# asserv-pami.net
KiCad netlist of a schematic drawn in EAGLE
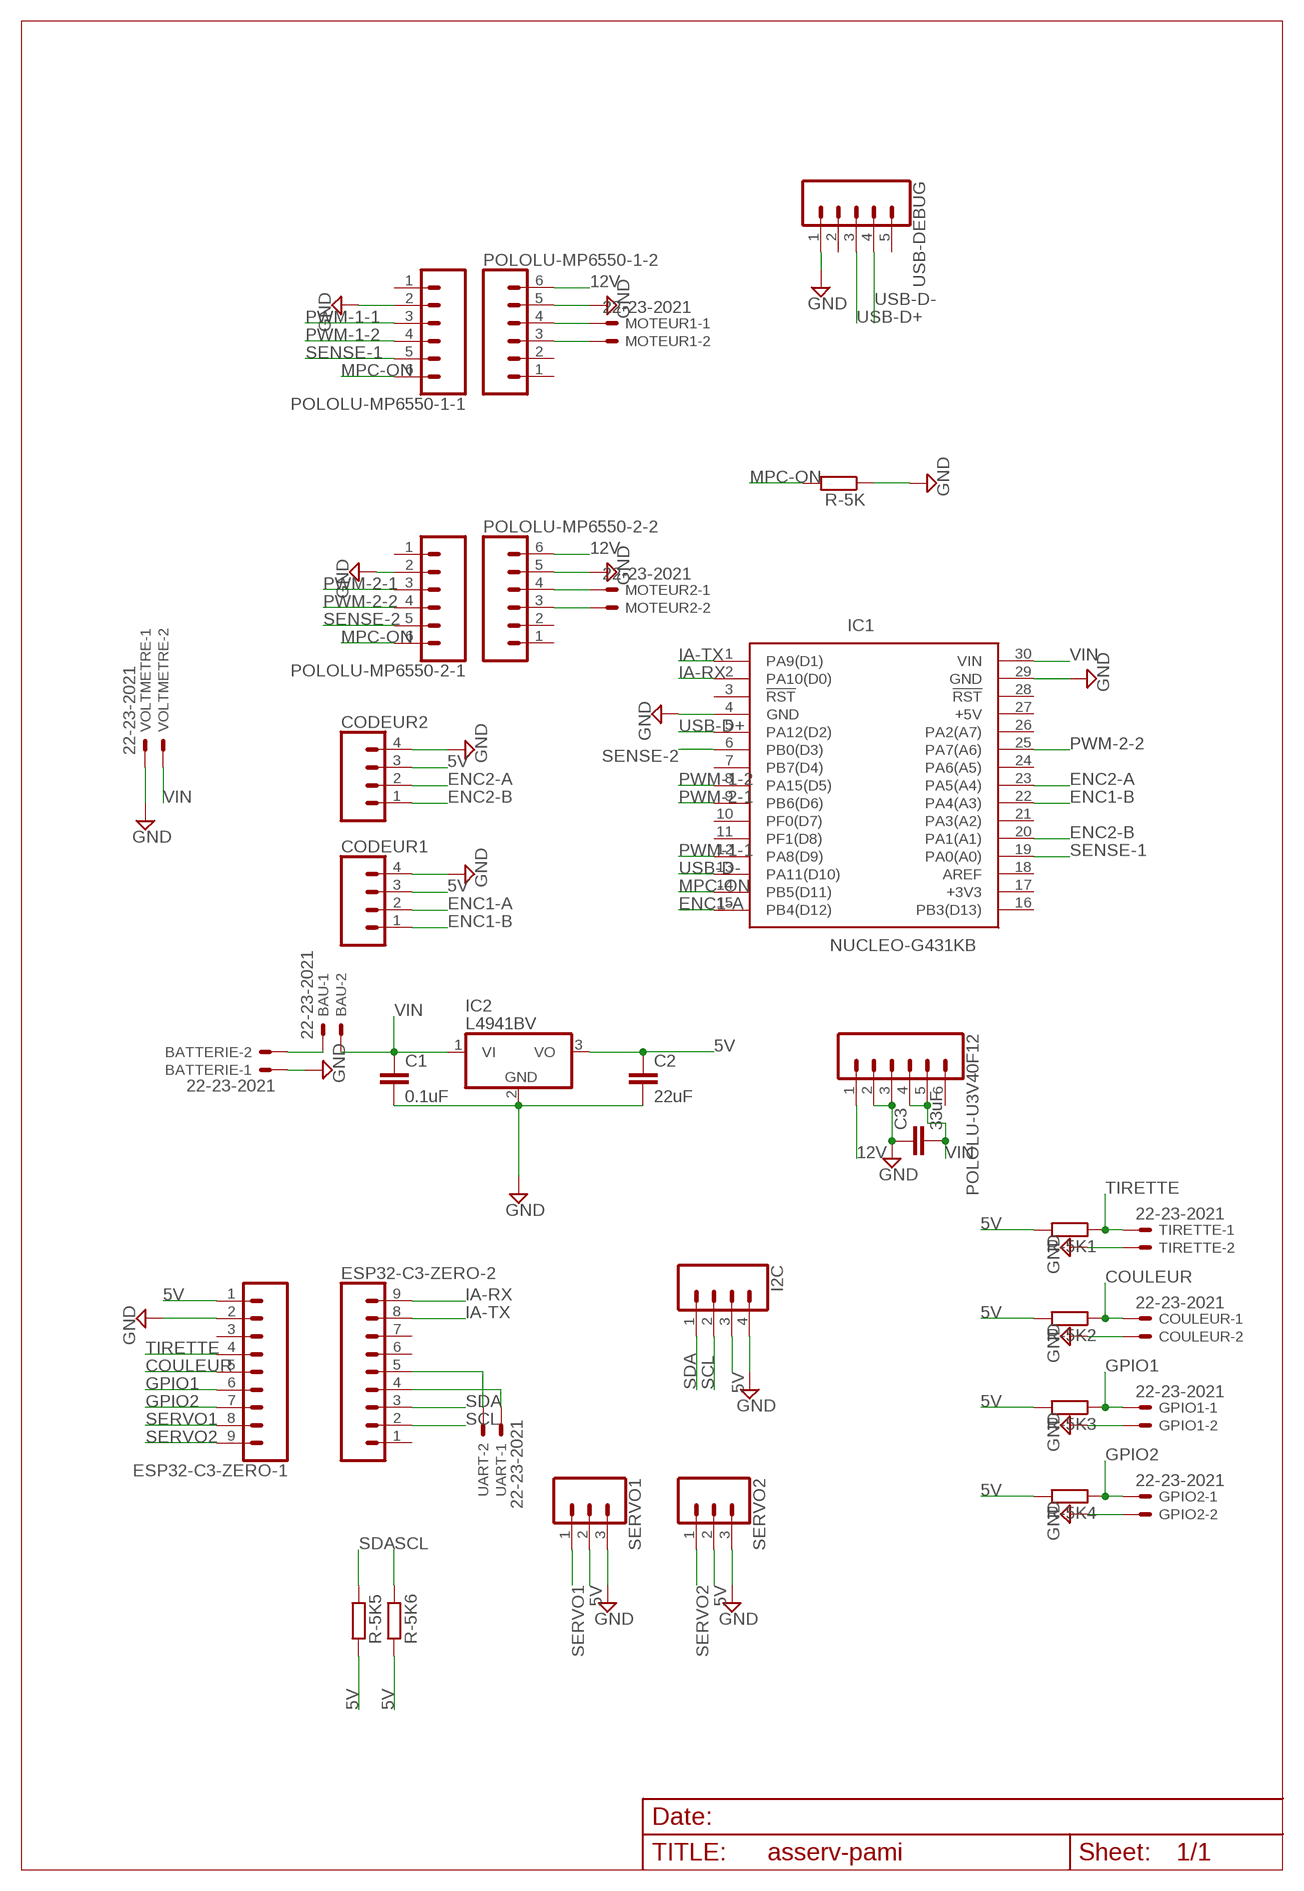
[diagram p0: schematic, sheet 1]

(export (version "E")
  (design (tool "Eeschema 10.0.6"))
  (components
    (comp (ref "BATTERIE")
      (value "22-23-2021")
      (footprint "eagle-import:22-23-2021")
      (fields (field (name "MF") "MOLEX"))
      (libsource (lib "eagle-import") (part "22-23-2021"))
    )
    (comp (ref "BAU")
      (value "22-23-2021")
      (footprint "eagle-import:22-23-2021")
      (fields (field (name "MF") "MOLEX"))
      (libsource (lib "eagle-import") (part "22-23-2021"))
    )
    (comp (ref "C1")
      (value "0.1uF")
      (footprint "eagle-import:C5B2.5")
      (libsource (lib "eagle-import") (part "C5/2.5"))
    )
    (comp (ref "C2")
      (value "22uF")
      (footprint "eagle-import:C5B2.5")
      (libsource (lib "eagle-import") (part "C5/2.5"))
    )
    (comp (ref "C3")
      (value "33uF")
      (footprint "eagle-import:C5B2.5")
      (libsource (lib "eagle-import") (part "C5/2.5"))
    )
    (comp (ref "CODEUR1")
      (value "CONN_04PTH")
      (footprint "eagle-import:1X04")
      (libsource (lib "eagle-import") (part "CONN_04PTH"))
    )
    (comp (ref "CODEUR2")
      (value "CONN_04PTH")
      (footprint "eagle-import:1X04")
      (libsource (lib "eagle-import") (part "CONN_04PTH"))
    )
    (comp (ref "COULEUR")
      (value "22-23-2021")
      (footprint "eagle-import:22-23-2021")
      (fields (field (name "MF") "MOLEX"))
      (libsource (lib "eagle-import") (part "22-23-2021"))
    )
    (comp (ref "ESP32-C3-ZERO-1")
      (value "CONN_09LONGPADS")
      (footprint "eagle-import:1X09_LONGPADS")
      (libsource (lib "eagle-import") (part "CONN_09LONGPADS"))
    )
    (comp (ref "ESP32-C3-ZERO-2")
      (value "CONN_09LONGPADS")
      (footprint "eagle-import:1X09_LONGPADS")
      (libsource (lib "eagle-import") (part "CONN_09LONGPADS"))
    )
    (comp (ref "GPIO1")
      (value "22-23-2021")
      (footprint "eagle-import:22-23-2021")
      (fields (field (name "MF") "MOLEX"))
      (libsource (lib "eagle-import") (part "22-23-2021"))
    )
    (comp (ref "GPIO2")
      (value "22-23-2021")
      (footprint "eagle-import:22-23-2021")
      (fields (field (name "MF") "MOLEX"))
      (libsource (lib "eagle-import") (part "22-23-2021"))
    )
    (comp (ref "I2C")
      (value "CONN_04PTH")
      (footprint "eagle-import:1X04")
      (libsource (lib "eagle-import") (part "CONN_04PTH"))
    )
    (comp (ref "IC1")
      (value "NUCLEO-G431KB")
      (footprint "eagle-import:DIPS1524W66P254L5029H1500Q30N")
      (fields (field (name "ARROW_PART_NUMBER") "NUCLEO-F303K8") (field (name "RS_PART_NUMBER") "9092862"))
      (libsource (lib "eagle-import") (part "NUCLEO-G431KB"))
    )
    (comp (ref "IC2")
      (value "L4941BV")
      (footprint "eagle-import:TO220V")
      (libsource (lib "eagle-import") (part "78TV05"))
    )
    (comp (ref "MOTEUR1")
      (value "22-23-2021")
      (footprint "eagle-import:22-23-2021")
      (fields (field (name "MF") "MOLEX"))
      (libsource (lib "eagle-import") (part "22-23-2021"))
    )
    (comp (ref "MOTEUR2")
      (value "22-23-2021")
      (footprint "eagle-import:22-23-2021")
      (fields (field (name "MF") "MOLEX"))
      (libsource (lib "eagle-import") (part "22-23-2021"))
    )
    (comp (ref "POLOLU-MP6550-1-1")
      (value "CONN_06NO_SILK_FEMALE_PTH")
      (footprint "eagle-import:1X06_NO_SILK")
      (libsource (lib "eagle-import") (part "CONN_06NO_SILK_FEMALE_PTH"))
    )
    (comp (ref "POLOLU-MP6550-1-2")
      (value "CONN_06NO_SILK_FEMALE_PTH")
      (footprint "eagle-import:1X06_NO_SILK")
      (libsource (lib "eagle-import") (part "CONN_06NO_SILK_FEMALE_PTH"))
    )
    (comp (ref "POLOLU-MP6550-2-1")
      (value "CONN_06NO_SILK_FEMALE_PTH")
      (footprint "eagle-import:1X06_NO_SILK")
      (libsource (lib "eagle-import") (part "CONN_06NO_SILK_FEMALE_PTH"))
    )
    (comp (ref "POLOLU-MP6550-2-2")
      (value "CONN_06NO_SILK_FEMALE_PTH")
      (footprint "eagle-import:1X06_NO_SILK")
      (libsource (lib "eagle-import") (part "CONN_06NO_SILK_FEMALE_PTH"))
    )
    (comp (ref "POLOLU-U3V40F12")
      (value "CONN_06NO_SILK_FEMALE_PTH")
      (footprint "eagle-import:1X06_NO_SILK")
      (libsource (lib "eagle-import") (part "CONN_06NO_SILK_FEMALE_PTH"))
    )
    (comp (ref "R-5K")
      (value "R-EU_0204/7")
      (footprint "eagle-import:0204_7")
      (libsource (lib "eagle-import") (part "R-EU_0204/7"))
    )
    (comp (ref "R-5K1")
      (value "R-EU_0204/7")
      (footprint "eagle-import:0204_7")
      (libsource (lib "eagle-import") (part "R-EU_0204/7"))
    )
    (comp (ref "R-5K2")
      (value "R-EU_0204/7")
      (footprint "eagle-import:0204_7")
      (libsource (lib "eagle-import") (part "R-EU_0204/7"))
    )
    (comp (ref "R-5K3")
      (value "R-EU_0204/7")
      (footprint "eagle-import:0204_7")
      (libsource (lib "eagle-import") (part "R-EU_0204/7"))
    )
    (comp (ref "R-5K4")
      (value "R-EU_0204/7")
      (footprint "eagle-import:0204_7")
      (libsource (lib "eagle-import") (part "R-EU_0204/7"))
    )
    (comp (ref "R-5K5")
      (value "R-EU_0204/7")
      (footprint "eagle-import:0204_7")
      (libsource (lib "eagle-import") (part "R-EU_0204/7"))
    )
    (comp (ref "R-5K6")
      (value "R-EU_0204/7")
      (footprint "eagle-import:0204_7")
      (libsource (lib "eagle-import") (part "R-EU_0204/7"))
    )
    (comp (ref "SERVO1")
      (value "CONN_03LONGPADS")
      (footprint "eagle-import:1X03_LONGPADS")
      (libsource (lib "eagle-import") (part "CONN_03LONGPADS"))
    )
    (comp (ref "SERVO2")
      (value "CONN_03LONGPADS")
      (footprint "eagle-import:1X03_LONGPADS")
      (libsource (lib "eagle-import") (part "CONN_03LONGPADS"))
    )
    (comp (ref "TIRETTE")
      (value "22-23-2021")
      (footprint "eagle-import:22-23-2021")
      (fields (field (name "MF") "MOLEX"))
      (libsource (lib "eagle-import") (part "22-23-2021"))
    )
    (comp (ref "UART")
      (value "22-23-2021")
      (footprint "eagle-import:22-23-2021")
      (fields (field (name "MF") "MOLEX"))
      (libsource (lib "eagle-import") (part "22-23-2021"))
    )
    (comp (ref "USB-DEBUG")
      (value "CONN_05NO_SILK")
      (footprint "eagle-import:1X05_NO_SILK")
      (libsource (lib "eagle-import") (part "CONN_05NO_SILK"))
    )
    (comp (ref "VOLTMETRE")
      (value "22-23-2021")
      (footprint "eagle-import:22-23-2021")
      (fields (field (name "MF") "MOLEX"))
      (libsource (lib "eagle-import") (part "22-23-2021"))
    )
  )
  (nets
    (net (code "1") (name "/5V") (class "Default")
      (node (ref "C2") (pin "1") (pinfunction "1_1") (pintype "passive"))
      (node (ref "CODEUR1") (pin "3") (pinfunction "3_3") (pintype "passive"))
      (node (ref "CODEUR2") (pin "3") (pinfunction "3_3") (pintype "passive"))
      (node (ref "ESP32-C3-ZERO-1") (pin "1") (pinfunction "1_1") (pintype "passive"))
      (node (ref "I2C") (pin "3") (pinfunction "3_3") (pintype "passive"))
      (node (ref "IC2") (pin "3") (pinfunction "VO_3") (pintype "passive"))
      (node (ref "R-5K1") (pin "2") (pinfunction "2_2") (pintype "passive"))
      (node (ref "R-5K2") (pin "2") (pinfunction "2_2") (pintype "passive"))
      (node (ref "R-5K3") (pin "2") (pinfunction "2_2") (pintype "passive"))
      (node (ref "R-5K4") (pin "2") (pinfunction "2_2") (pintype "passive"))
      (node (ref "R-5K5") (pin "2") (pinfunction "2_2") (pintype "passive"))
      (node (ref "R-5K6") (pin "2") (pinfunction "2_2") (pintype "passive"))
      (node (ref "SERVO1") (pin "2") (pinfunction "2_2") (pintype "passive"))
      (node (ref "SERVO2") (pin "2") (pinfunction "2_2") (pintype "passive"))
    )
    (net (code "2") (name "/12V") (class "Default")
      (node (ref "POLOLU-MP6550-1-2") (pin "6") (pinfunction "6_6") (pintype "passive"))
      (node (ref "POLOLU-MP6550-2-2") (pin "6") (pinfunction "6_6") (pintype "passive"))
      (node (ref "POLOLU-U3V40F12") (pin "1") (pinfunction "1_1") (pintype "passive"))
    )
    (net (code "3") (name "/COULEUR") (class "Default")
      (node (ref "COULEUR") (pin "1") (pinfunction "S_1") (pintype "passive"))
      (node (ref "ESP32-C3-ZERO-1") (pin "5") (pinfunction "5_5") (pintype "passive"))
      (node (ref "R-5K2") (pin "1") (pinfunction "1_1") (pintype "passive"))
    )
    (net (code "4") (name "/ENC1-A") (class "Default")
      (node (ref "CODEUR1") (pin "2") (pinfunction "2_2") (pintype "passive"))
      (node (ref "IC1") (pin "15") (pinfunction "PB4(D12)_15") (pintype "bidirectional"))
    )
    (net (code "5") (name "/ENC1-B") (class "Default")
      (node (ref "CODEUR1") (pin "1") (pinfunction "1_1") (pintype "passive"))
      (node (ref "IC1") (pin "22") (pinfunction "PA4(A3)_22") (pintype "bidirectional"))
    )
    (net (code "6") (name "/ENC2-A") (class "Default")
      (node (ref "CODEUR2") (pin "2") (pinfunction "2_2") (pintype "passive"))
      (node (ref "IC1") (pin "23") (pinfunction "PA5(A4)_23") (pintype "bidirectional"))
    )
    (net (code "7") (name "/ENC2-B") (class "Default")
      (node (ref "CODEUR2") (pin "1") (pinfunction "1_1") (pintype "passive"))
      (node (ref "IC1") (pin "20") (pinfunction "PA1(A1)_20") (pintype "bidirectional"))
    )
    (net (code "8") (name "/GPIO1") (class "Default")
      (node (ref "ESP32-C3-ZERO-1") (pin "6") (pinfunction "6_6") (pintype "passive"))
      (node (ref "GPIO1") (pin "1") (pinfunction "S_1") (pintype "passive"))
      (node (ref "R-5K3") (pin "1") (pinfunction "1_1") (pintype "passive"))
    )
    (net (code "9") (name "/GPIO2") (class "Default")
      (node (ref "ESP32-C3-ZERO-1") (pin "7") (pinfunction "7_7") (pintype "passive"))
      (node (ref "GPIO2") (pin "1") (pinfunction "S_1") (pintype "passive"))
      (node (ref "R-5K4") (pin "1") (pinfunction "1_1") (pintype "passive"))
    )
    (net (code "10") (name "/IA-RX") (class "Default")
      (node (ref "ESP32-C3-ZERO-2") (pin "9") (pinfunction "9_9") (pintype "passive"))
      (node (ref "IC1") (pin "2") (pinfunction "PA10(D0)_2") (pintype "bidirectional"))
    )
    (net (code "11") (name "/IA-TX") (class "Default")
      (node (ref "ESP32-C3-ZERO-2") (pin "8") (pinfunction "8_8") (pintype "passive"))
      (node (ref "IC1") (pin "1") (pinfunction "PA9(D1)_1") (pintype "bidirectional"))
    )
    (net (code "12") (name "/MPC-ON") (class "Default")
      (node (ref "IC1") (pin "14") (pinfunction "PB5(D11)_14") (pintype "bidirectional"))
      (node (ref "POLOLU-MP6550-1-1") (pin "6") (pinfunction "6_6") (pintype "passive"))
      (node (ref "POLOLU-MP6550-2-1") (pin "6") (pinfunction "6_6") (pintype "passive"))
      (node (ref "R-5K") (pin "2") (pinfunction "2_2") (pintype "passive"))
    )
    (net (code "13") (name "/PWM-1-1") (class "Default")
      (node (ref "IC1") (pin "12") (pinfunction "PA8(D9)_12") (pintype "bidirectional"))
      (node (ref "POLOLU-MP6550-1-1") (pin "3") (pinfunction "3_3") (pintype "passive"))
    )
    (net (code "14") (name "/PWM-1-2") (class "Default")
      (node (ref "IC1") (pin "8") (pinfunction "PA15(D5)_8") (pintype "bidirectional"))
      (node (ref "POLOLU-MP6550-1-1") (pin "4") (pinfunction "4_4") (pintype "passive"))
    )
    (net (code "15") (name "/PWM-2-1") (class "Default")
      (node (ref "IC1") (pin "9") (pinfunction "PB6(D6)_9") (pintype "bidirectional"))
      (node (ref "POLOLU-MP6550-2-1") (pin "3") (pinfunction "3_3") (pintype "passive"))
    )
    (net (code "16") (name "/PWM-2-2") (class "Default")
      (node (ref "IC1") (pin "25") (pinfunction "PA7(A6)_25") (pintype "bidirectional"))
      (node (ref "POLOLU-MP6550-2-1") (pin "4") (pinfunction "4_4") (pintype "passive"))
    )
    (net (code "17") (name "/SCL") (class "Default")
      (node (ref "ESP32-C3-ZERO-2") (pin "2") (pinfunction "2_2") (pintype "passive"))
      (node (ref "I2C") (pin "2") (pinfunction "2_2") (pintype "passive"))
      (node (ref "R-5K6") (pin "1") (pinfunction "1_1") (pintype "passive"))
    )
    (net (code "18") (name "/SDA") (class "Default")
      (node (ref "ESP32-C3-ZERO-2") (pin "3") (pinfunction "3_3") (pintype "passive"))
      (node (ref "I2C") (pin "1") (pinfunction "1_1") (pintype "passive"))
      (node (ref "R-5K5") (pin "1") (pinfunction "1_1") (pintype "passive"))
    )
    (net (code "19") (name "/SENSE-1") (class "Default")
      (node (ref "IC1") (pin "19") (pinfunction "PA0(A0)_19") (pintype "bidirectional"))
      (node (ref "POLOLU-MP6550-1-1") (pin "5") (pinfunction "5_5") (pintype "passive"))
    )
    (net (code "20") (name "/SENSE-2") (class "Default")
      (node (ref "IC1") (pin "6") (pinfunction "PB0(D3)_6") (pintype "bidirectional"))
      (node (ref "POLOLU-MP6550-2-1") (pin "5") (pinfunction "5_5") (pintype "passive"))
    )
    (net (code "21") (name "/SERVO1") (class "Default")
      (node (ref "ESP32-C3-ZERO-1") (pin "8") (pinfunction "8_8") (pintype "passive"))
      (node (ref "SERVO1") (pin "1") (pinfunction "1_1") (pintype "passive"))
    )
    (net (code "22") (name "/SERVO2") (class "Default")
      (node (ref "ESP32-C3-ZERO-1") (pin "9") (pinfunction "9_9") (pintype "passive"))
      (node (ref "SERVO2") (pin "1") (pinfunction "1_1") (pintype "passive"))
    )
    (net (code "23") (name "/TIRETTE") (class "Default")
      (node (ref "ESP32-C3-ZERO-1") (pin "4") (pinfunction "4_4") (pintype "passive"))
      (node (ref "R-5K1") (pin "1") (pinfunction "1_1") (pintype "passive"))
      (node (ref "TIRETTE") (pin "1") (pinfunction "S_1") (pintype "passive"))
    )
    (net (code "24") (name "/USB-D+") (class "Default")
      (node (ref "IC1") (pin "5") (pinfunction "PA12(D2)_5") (pintype "bidirectional"))
      (node (ref "USB-DEBUG") (pin "3") (pinfunction "3_3") (pintype "passive"))
    )
    (net (code "25") (name "/USB-D-") (class "Default")
      (node (ref "IC1") (pin "13") (pinfunction "PA11(D10)_13") (pintype "bidirectional"))
      (node (ref "USB-DEBUG") (pin "4") (pinfunction "4_4") (pintype "passive"))
    )
    (net (code "26") (name "/VIN") (class "Default")
      (node (ref "BAU") (pin "2") (pinfunction "S_2") (pintype "passive"))
      (node (ref "C1") (pin "1") (pinfunction "1_1") (pintype "passive"))
      (node (ref "C3") (pin "2") (pinfunction "2_2") (pintype "passive"))
      (node (ref "IC1") (pin "30") (pinfunction "VIN_30") (pintype "passive"))
      (node (ref "IC2") (pin "1") (pinfunction "VI_1") (pintype "input"))
      (node (ref "POLOLU-U3V40F12") (pin "4") (pinfunction "4_4") (pintype "passive"))
      (node (ref "POLOLU-U3V40F12") (pin "5") (pinfunction "5_5") (pintype "passive"))
      (node (ref "VOLTMETRE") (pin "2") (pinfunction "S_2") (pintype "passive"))
    )
    (net (code "27") (name "GND") (class "Default")
      (node (ref "BATTERIE") (pin "1") (pinfunction "S_1") (pintype "passive"))
      (node (ref "C1") (pin "2") (pinfunction "2_2") (pintype "passive"))
      (node (ref "C2") (pin "2") (pinfunction "2_2") (pintype "passive"))
      (node (ref "C3") (pin "1") (pinfunction "1_1") (pintype "passive"))
      (node (ref "CODEUR1") (pin "4") (pinfunction "4_4") (pintype "passive"))
      (node (ref "CODEUR2") (pin "4") (pinfunction "4_4") (pintype "passive"))
      (node (ref "COULEUR") (pin "2") (pinfunction "S_2") (pintype "passive"))
      (node (ref "ESP32-C3-ZERO-1") (pin "2") (pinfunction "2_2") (pintype "passive"))
      (node (ref "GPIO1") (pin "2") (pinfunction "S_2") (pintype "passive"))
      (node (ref "GPIO2") (pin "2") (pinfunction "S_2") (pintype "passive"))
      (node (ref "I2C") (pin "4") (pinfunction "4_4") (pintype "passive"))
      (node (ref "IC1") (pin "29") (pinfunction "GND_29") (pintype "passive"))
      (node (ref "IC1") (pin "4") (pinfunction "GND_4") (pintype "passive"))
      (node (ref "IC2") (pin "2") (pinfunction "GND_2") (pintype "passive"))
      (node (ref "POLOLU-MP6550-1-1") (pin "2") (pinfunction "2_2") (pintype "passive"))
      (node (ref "POLOLU-MP6550-1-2") (pin "5") (pinfunction "5_5") (pintype "passive"))
      (node (ref "POLOLU-MP6550-2-1") (pin "2") (pinfunction "2_2") (pintype "passive"))
      (node (ref "POLOLU-MP6550-2-2") (pin "5") (pinfunction "5_5") (pintype "passive"))
      (node (ref "POLOLU-U3V40F12") (pin "2") (pinfunction "2_2") (pintype "passive"))
      (node (ref "POLOLU-U3V40F12") (pin "3") (pinfunction "3_3") (pintype "passive"))
      (node (ref "R-5K") (pin "1") (pinfunction "1_1") (pintype "passive"))
      (node (ref "SERVO1") (pin "3") (pinfunction "3_3") (pintype "passive"))
      (node (ref "SERVO2") (pin "3") (pinfunction "3_3") (pintype "passive"))
      (node (ref "TIRETTE") (pin "2") (pinfunction "S_2") (pintype "passive"))
      (node (ref "USB-DEBUG") (pin "1") (pinfunction "1_1") (pintype "passive"))
      (node (ref "VOLTMETRE") (pin "1") (pinfunction "S_1") (pintype "passive"))
    )
    (net (code "28") (name "Net-(BATTERIEB-S)") (class "Default")
      (node (ref "BATTERIE") (pin "2") (pinfunction "S_2") (pintype "passive"))
      (node (ref "BAU") (pin "1") (pinfunction "S_1") (pintype "passive"))
    )
    (net (code "29") (name "Net-(MOTEUR1A-S)") (class "Default")
      (node (ref "MOTEUR1") (pin "1") (pinfunction "S_1") (pintype "passive"))
      (node (ref "POLOLU-MP6550-1-2") (pin "4") (pinfunction "4_4") (pintype "passive"))
    )
    (net (code "30") (name "Net-(MOTEUR1B-S)") (class "Default")
      (node (ref "MOTEUR1") (pin "2") (pinfunction "S_2") (pintype "passive"))
      (node (ref "POLOLU-MP6550-1-2") (pin "3") (pinfunction "3_3") (pintype "passive"))
    )
    (net (code "31") (name "Net-(MOTEUR2A-S)") (class "Default")
      (node (ref "MOTEUR2") (pin "1") (pinfunction "S_1") (pintype "passive"))
      (node (ref "POLOLU-MP6550-2-2") (pin "4") (pinfunction "4_4") (pintype "passive"))
    )
    (net (code "32") (name "Net-(MOTEUR2B-S)") (class "Default")
      (node (ref "MOTEUR2") (pin "2") (pinfunction "S_2") (pintype "passive"))
      (node (ref "POLOLU-MP6550-2-2") (pin "3") (pinfunction "3_3") (pintype "passive"))
    )
    (net (code "33") (name "Net-(UARTA-S)") (class "Default")
      (node (ref "ESP32-C3-ZERO-2") (pin "4") (pinfunction "4_4") (pintype "passive"))
      (node (ref "UART") (pin "1") (pinfunction "S_1") (pintype "passive"))
    )
    (net (code "34") (name "Net-(UARTB-S)") (class "Default")
      (node (ref "ESP32-C3-ZERO-2") (pin "5") (pinfunction "5_5") (pintype "passive"))
      (node (ref "UART") (pin "2") (pinfunction "S_2") (pintype "passive"))
    )
    (net (code "35") (name "unconnected-(ESP32-C3-ZERO-1-Pad3)") (class "Default")
      (node (ref "ESP32-C3-ZERO-1") (pin "3") (pinfunction "3_3") (pintype "passive"))
    )
    (net (code "36") (name "unconnected-(ESP32-C3-ZERO-2-Pad1)") (class "Default")
      (node (ref "ESP32-C3-ZERO-2") (pin "1") (pinfunction "1_1") (pintype "passive"))
    )
    (net (code "37") (name "unconnected-(ESP32-C3-ZERO-2-Pad6)") (class "Default")
      (node (ref "ESP32-C3-ZERO-2") (pin "6") (pinfunction "6_6") (pintype "passive"))
    )
    (net (code "38") (name "unconnected-(ESP32-C3-ZERO-2-Pad7)") (class "Default")
      (node (ref "ESP32-C3-ZERO-2") (pin "7") (pinfunction "7_7") (pintype "passive"))
    )
    (net (code "39") (name "unconnected-(IC1-+3V3-Pad17)") (class "Default")
      (node (ref "IC1") (pin "17") (pinfunction "+3V3_17") (pintype "passive"))
    )
    (net (code "40") (name "unconnected-(IC1-+5V-Pad27)") (class "Default")
      (node (ref "IC1") (pin "27") (pinfunction "+5V_27") (pintype "passive"))
    )
    (net (code "41") (name "unconnected-(IC1-AREF-Pad18)") (class "Default")
      (node (ref "IC1") (pin "18") (pinfunction "AREF_18") (pintype "passive"))
    )
    (net (code "42") (name "unconnected-(IC1-PA2(A7)-Pad26)") (class "Default")
      (node (ref "IC1") (pin "26") (pinfunction "PA2(A7)_26") (pintype "bidirectional"))
    )
    (net (code "43") (name "unconnected-(IC1-PA3(A2)-Pad21)") (class "Default")
      (node (ref "IC1") (pin "21") (pinfunction "PA3(A2)_21") (pintype "bidirectional"))
    )
    (net (code "44") (name "unconnected-(IC1-PA6(A5)-Pad24)") (class "Default")
      (node (ref "IC1") (pin "24") (pinfunction "PA6(A5)_24") (pintype "bidirectional"))
    )
    (net (code "45") (name "unconnected-(IC1-PB3(D13)-Pad16)") (class "Default")
      (node (ref "IC1") (pin "16") (pinfunction "PB3(D13)_16") (pintype "bidirectional"))
    )
    (net (code "46") (name "unconnected-(IC1-PB7(D4)-Pad7)") (class "Default")
      (node (ref "IC1") (pin "7") (pinfunction "PB7(D4)_7") (pintype "bidirectional"))
    )
    (net (code "47") (name "unconnected-(IC1-PF0(D7)-Pad10)") (class "Default")
      (node (ref "IC1") (pin "10") (pinfunction "PF0(D7)_10") (pintype "bidirectional"))
    )
    (net (code "48") (name "unconnected-(IC1-PF1(D8)-Pad11)") (class "Default")
      (node (ref "IC1") (pin "11") (pinfunction "PF1(D8)_11") (pintype "bidirectional"))
    )
    (net (code "49") (name "unconnected-(IC1-~{RST}-Pad3)") (class "Default")
      (node (ref "IC1") (pin "3") (pinfunction "~{RST}_3") (pintype "bidirectional"))
    )
    (net (code "50") (name "unconnected-(IC1-~{RST}-Pad28)") (class "Default")
      (node (ref "IC1") (pin "28") (pinfunction "~{RST}_28") (pintype "bidirectional"))
    )
    (net (code "51") (name "unconnected-(POLOLU-MP6550-1-1-Pad1)") (class "Default")
      (node (ref "POLOLU-MP6550-1-1") (pin "1") (pinfunction "1_1") (pintype "passive"))
    )
    (net (code "52") (name "unconnected-(POLOLU-MP6550-1-2-Pad1)") (class "Default")
      (node (ref "POLOLU-MP6550-1-2") (pin "1") (pinfunction "1_1") (pintype "passive"))
    )
    (net (code "53") (name "unconnected-(POLOLU-MP6550-1-2-Pad2)") (class "Default")
      (node (ref "POLOLU-MP6550-1-2") (pin "2") (pinfunction "2_2") (pintype "passive"))
    )
    (net (code "54") (name "unconnected-(POLOLU-MP6550-2-1-Pad1)") (class "Default")
      (node (ref "POLOLU-MP6550-2-1") (pin "1") (pinfunction "1_1") (pintype "passive"))
    )
    (net (code "55") (name "unconnected-(POLOLU-MP6550-2-2-Pad1)") (class "Default")
      (node (ref "POLOLU-MP6550-2-2") (pin "1") (pinfunction "1_1") (pintype "passive"))
    )
    (net (code "56") (name "unconnected-(POLOLU-MP6550-2-2-Pad2)") (class "Default")
      (node (ref "POLOLU-MP6550-2-2") (pin "2") (pinfunction "2_2") (pintype "passive"))
    )
    (net (code "57") (name "unconnected-(POLOLU-U3V40F12-Pad6)") (class "Default")
      (node (ref "POLOLU-U3V40F12") (pin "6") (pinfunction "6_6") (pintype "passive"))
    )
    (net (code "58") (name "unconnected-(USB-DEBUG-Pad2)") (class "Default")
      (node (ref "USB-DEBUG") (pin "2") (pinfunction "2_2") (pintype "passive"))
    )
    (net (code "59") (name "unconnected-(USB-DEBUG-Pad5)") (class "Default")
      (node (ref "USB-DEBUG") (pin "5") (pinfunction "5_5") (pintype "passive"))
    )
  )
)
